# S7CAS-PLEIADES-CARTE-MERE_P07_DAC.net
KiCad netlist of a schematic drawn in Altium Designer
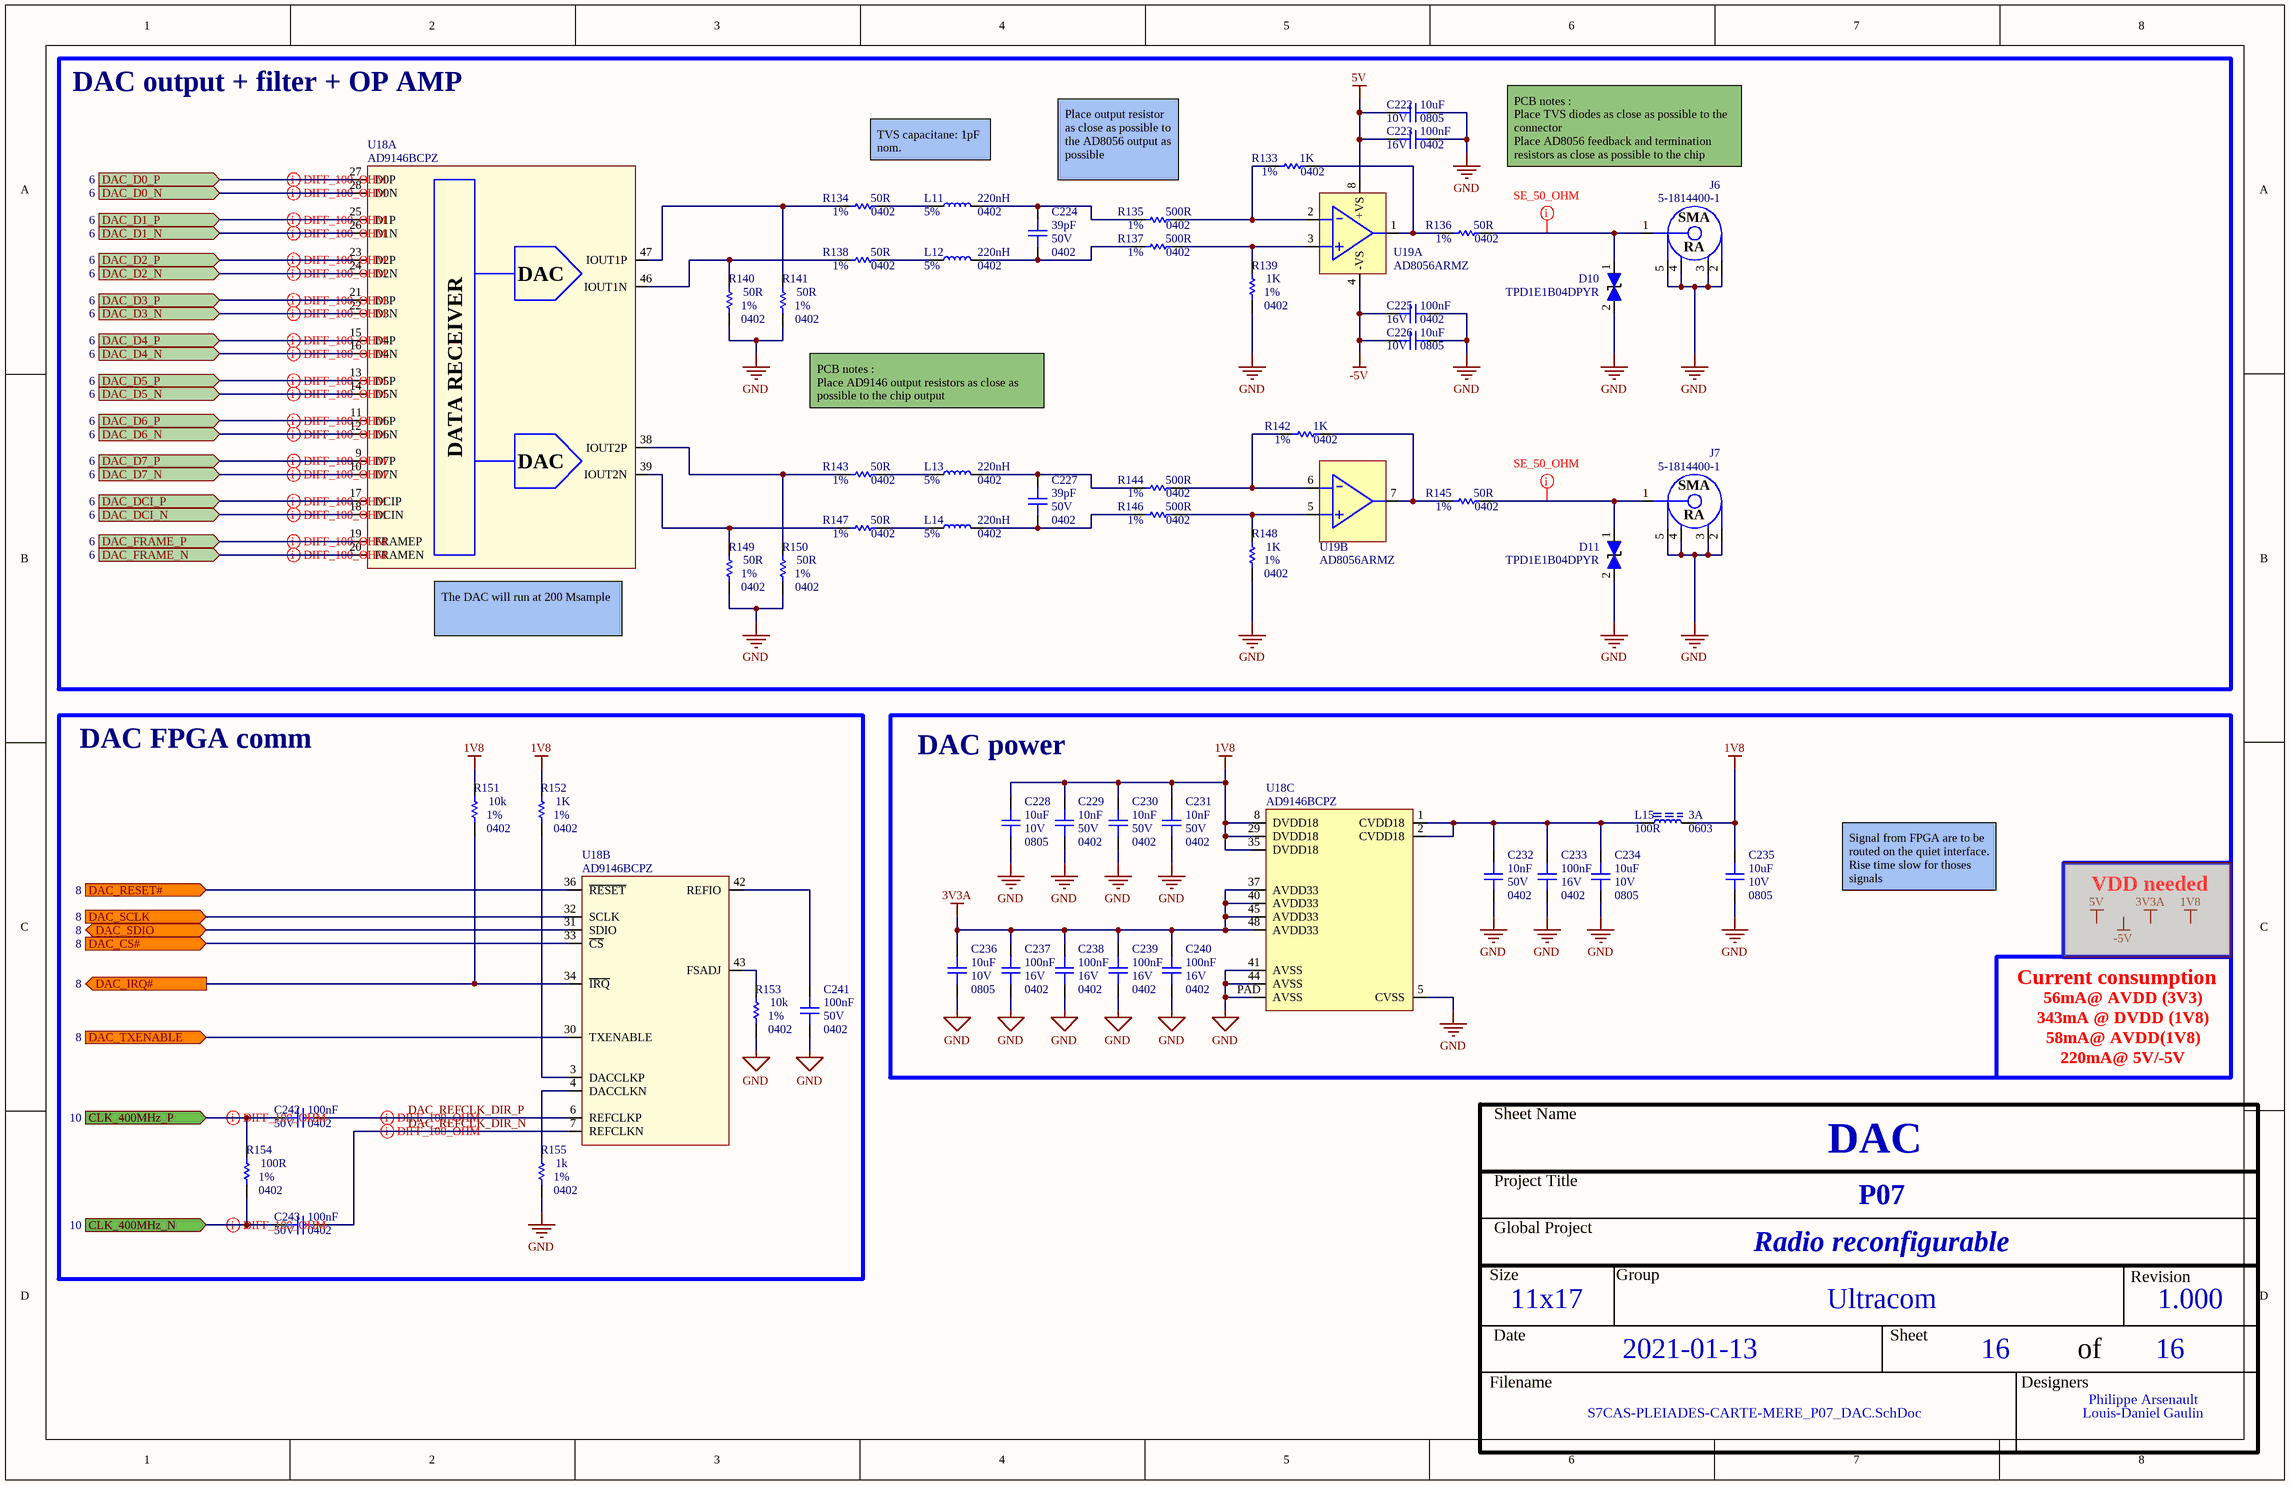
[diagram p0: S7CAS-PLEIADES-CARTE-MERE_P07_DAC.SchDoc]

(export (version "E")
  (design (tool "Eeschema 10.0.6"))
  (components
    (comp (ref "C222")
      (value "10uF")
      (footprint "CAP_0805")
      (description "CAP - 0805")
      (fields
        (field (name "MFG") "CL21B106KPQNNNE")
        (field (name "VOLTAGE") "10V")
        (field (name "PACKAGE") "0805")
        (field (name "CREATEDBY") "Jonathan Bouchard")
      )
      (libsource (lib "S7CAS_LIB2021") (part "CAP - 0805"))
    )
    (comp (ref "C223")
      (value "100nF")
      (footprint "CAP_0402")
      (description "CAP - 0402")
      (fields
        (field (name "MFG PART NUMBER") "CL05B104KO5NNNC")
        (field (name "VOLTAGE") "16V")
        (field (name "PACKAGE") "0402")
        (field (name "CREATEDBY") "Jonathan Bouchard")
      )
      (libsource (lib "S7CAS_LIB2021") (part "CAP - 0402"))
    )
    (comp (ref "C224")
      (value "39pF")
      (footprint "CAP_0402")
      (description "CAP - 0402")
      (fields
        (field (name "VOLTAGE") "50V")
        (field (name "PACKAGE") "0402")
        (field (name "CREATEDBY") "Jonathan Bouchard")
      )
      (libsource (lib "S7CAS_LIB2021") (part "CAP - 0402"))
    )
    (comp (ref "C225")
      (value "100nF")
      (footprint "CAP_0402")
      (description "CAP - 0402")
      (fields
        (field (name "MFG PART NUMBER") "CL05B104KO5NNNC")
        (field (name "VOLTAGE") "16V")
        (field (name "PACKAGE") "0402")
        (field (name "CREATEDBY") "Jonathan Bouchard")
      )
      (libsource (lib "S7CAS_LIB2021") (part "CAP - 0402"))
    )
    (comp (ref "C226")
      (value "10uF")
      (footprint "CAP_0805")
      (description "CAP - 0805")
      (fields
        (field (name "MFG") "CL21B106KPQNNNE")
        (field (name "VOLTAGE") "10V")
        (field (name "PACKAGE") "0805")
        (field (name "CREATEDBY") "Jonathan Bouchard")
      )
      (libsource (lib "S7CAS_LIB2021") (part "CAP - 0805"))
    )
    (comp (ref "C227")
      (value "39pF")
      (footprint "CAP_0402")
      (description "CAP - 0402")
      (fields
        (field (name "VOLTAGE") "50V")
        (field (name "PACKAGE") "0402")
        (field (name "CREATEDBY") "Jonathan Bouchard")
      )
      (libsource (lib "S7CAS_LIB2021") (part "CAP - 0402"))
    )
    (comp (ref "C228")
      (value "10uF")
      (footprint "CAP_0805")
      (description "CAP - 0805")
      (fields
        (field (name "MFG") "CL21B106KPQNNNE")
        (field (name "VOLTAGE") "10V")
        (field (name "PACKAGE") "0805")
        (field (name "CREATEDBY") "Jonathan Bouchard")
      )
      (libsource (lib "S7CAS_LIB2021") (part "CAP - 0805"))
    )
    (comp (ref "C229")
      (value "10nF")
      (footprint "CAP_0402")
      (description "CAP - 0402")
      (fields
        (field (name "MFG PART NUMBER") "CL05B103KB5NNNC")
        (field (name "VOLTAGE") "50V")
        (field (name "PACKAGE") "0402")
        (field (name "CREATEDBY") "Jonathan Bouchard")
      )
      (libsource (lib "S7CAS_LIB2021") (part "CAP - 0402"))
    )
    (comp (ref "C230")
      (value "10nF")
      (footprint "CAP_0402")
      (description "CAP - 0402")
      (fields
        (field (name "MFG PART NUMBER") "CL05B103KB5NNNC")
        (field (name "VOLTAGE") "50V")
        (field (name "PACKAGE") "0402")
        (field (name "CREATEDBY") "Jonathan Bouchard")
      )
      (libsource (lib "S7CAS_LIB2021") (part "CAP - 0402"))
    )
    (comp (ref "C231")
      (value "10nF")
      (footprint "CAP_0402")
      (description "CAP - 0402")
      (fields
        (field (name "MFG PART NUMBER") "CL05B103KB5NNNC")
        (field (name "VOLTAGE") "50V")
        (field (name "PACKAGE") "0402")
        (field (name "CREATEDBY") "Jonathan Bouchard")
      )
      (libsource (lib "S7CAS_LIB2021") (part "CAP - 0402"))
    )
    (comp (ref "C232")
      (value "10nF")
      (footprint "CAP_0402")
      (description "CAP - 0402")
      (fields
        (field (name "MFG PART NUMBER") "CL05B103KB5NNNC")
        (field (name "VOLTAGE") "50V")
        (field (name "PACKAGE") "0402")
        (field (name "CREATEDBY") "Jonathan Bouchard")
      )
      (libsource (lib "S7CAS_LIB2021") (part "CAP - 0402"))
    )
    (comp (ref "C233")
      (value "100nF")
      (footprint "CAP_0402")
      (description "CAP - 0402")
      (fields
        (field (name "MFG PART NUMBER") "CL05B104KO5NNNC")
        (field (name "VOLTAGE") "16V")
        (field (name "PACKAGE") "0402")
        (field (name "CREATEDBY") "Jonathan Bouchard")
      )
      (libsource (lib "S7CAS_LIB2021") (part "CAP - 0402"))
    )
    (comp (ref "C234")
      (value "10uF")
      (footprint "CAP_0805")
      (description "CAP - 0805")
      (fields
        (field (name "MFG") "CL21B106KPQNNNE")
        (field (name "VOLTAGE") "10V")
        (field (name "PACKAGE") "0805")
        (field (name "CREATEDBY") "Jonathan Bouchard")
      )
      (libsource (lib "S7CAS_LIB2021") (part "CAP - 0805"))
    )
    (comp (ref "C235")
      (value "10uF")
      (footprint "CAP_0805")
      (description "CAP - 0805")
      (fields
        (field (name "MFG") "CL21B106KPQNNNE")
        (field (name "VOLTAGE") "10V")
        (field (name "PACKAGE") "0805")
        (field (name "CREATEDBY") "Jonathan Bouchard")
      )
      (libsource (lib "S7CAS_LIB2021") (part "CAP - 0805"))
    )
    (comp (ref "C236")
      (value "10uF")
      (footprint "CAP_0805")
      (description "CAP - 0805")
      (fields
        (field (name "MFG") "CL21B106KPQNNNE")
        (field (name "VOLTAGE") "10V")
        (field (name "PACKAGE") "0805")
        (field (name "CREATEDBY") "Jonathan Bouchard")
      )
      (libsource (lib "S7CAS_LIB2021") (part "CAP - 0805"))
    )
    (comp (ref "C237")
      (value "100nF")
      (footprint "CAP_0402")
      (description "CAP - 0402")
      (fields
        (field (name "MFG PART NUMBER") "CL05B104KO5NNNC")
        (field (name "VOLTAGE") "16V")
        (field (name "PACKAGE") "0402")
        (field (name "CREATEDBY") "Jonathan Bouchard")
      )
      (libsource (lib "S7CAS_LIB2021") (part "CAP - 0402"))
    )
    (comp (ref "C238")
      (value "100nF")
      (footprint "CAP_0402")
      (description "CAP - 0402")
      (fields
        (field (name "MFG PART NUMBER") "CL05B104KO5NNNC")
        (field (name "VOLTAGE") "16V")
        (field (name "PACKAGE") "0402")
        (field (name "CREATEDBY") "Jonathan Bouchard")
      )
      (libsource (lib "S7CAS_LIB2021") (part "CAP - 0402"))
    )
    (comp (ref "C239")
      (value "100nF")
      (footprint "CAP_0402")
      (description "CAP - 0402")
      (fields
        (field (name "MFG PART NUMBER") "CL05B104KO5NNNC")
        (field (name "VOLTAGE") "16V")
        (field (name "PACKAGE") "0402")
        (field (name "CREATEDBY") "Jonathan Bouchard")
      )
      (libsource (lib "S7CAS_LIB2021") (part "CAP - 0402"))
    )
    (comp (ref "C240")
      (value "100nF")
      (footprint "CAP_0402")
      (description "CAP - 0402")
      (fields
        (field (name "MFG PART NUMBER") "CL05B104KO5NNNC")
        (field (name "VOLTAGE") "16V")
        (field (name "PACKAGE") "0402")
        (field (name "CREATEDBY") "Jonathan Bouchard")
      )
      (libsource (lib "S7CAS_LIB2021") (part "CAP - 0402"))
    )
    (comp (ref "C241")
      (value "100nF")
      (footprint "CAP_0402")
      (description "CAP - 0402")
      (fields
        (field (name "VOLTAGE") "50V")
        (field (name "PACKAGE") "0402")
        (field (name "CREATEDBY") "Jonathan Bouchard")
      )
      (libsource (lib "S7CAS_LIB2021") (part "CAP - 0402"))
    )
    (comp (ref "C242")
      (value "100nF")
      (footprint "CAP_0402")
      (description "CAP - 0402")
      (fields
        (field (name "VOLTAGE") "50V")
        (field (name "PACKAGE") "0402")
        (field (name "CREATEDBY") "Jonathan Bouchard")
      )
      (libsource (lib "S7CAS_LIB2021") (part "CAP - 0402"))
    )
    (comp (ref "C243")
      (value "100nF")
      (footprint "CAP_0402")
      (description "CAP - 0402")
      (fields
        (field (name "VOLTAGE") "50V")
        (field (name "PACKAGE") "0402")
        (field (name "CREATEDBY") "Jonathan Bouchard")
      )
      (libsource (lib "S7CAS_LIB2021") (part "CAP - 0402"))
    )
    (comp (ref "D10")
      (value "TPD1E1B04DPYR")
      (footprint "TVS_DATA_TPD1E1B04DPYR")
      (description "TVS - TVS DIODE 3.6V 8.5V - 0402")
      (fields
        (field (name "CREATEDBY/DATE") "Keven Deslandes - 2018/10/19")
        (field (name "VERIFIEDBY") "Caroline Paulin - 28 janv 2019")
      )
      (libsource (lib "S7CAS_LIB2021") (part "TVS_DATA_TPD1E1B04DPYR"))
    )
    (comp (ref "D11")
      (value "TPD1E1B04DPYR")
      (footprint "TVS_DATA_TPD1E1B04DPYR")
      (description "TVS - TVS DIODE 3.6V 8.5V - 0402")
      (fields
        (field (name "CREATEDBY/DATE") "Keven Deslandes - 2018/10/19")
        (field (name "VERIFIEDBY") "Caroline Paulin - 28 janv 2019")
      )
      (libsource (lib "S7CAS_LIB2021") (part "TVS_DATA_TPD1E1B04DPYR"))
    )
    (comp (ref "J6")
      (value "5-1814400-1")
      (footprint "CONN_SMA_5-1814400-1")
      (description "CONN -  SMA JACK R/A 50 OHM - TH")
      (fields
        (field (name "MFG") "TE Connectivity AMP Connectors")
        (field (name "CREATEDBY") "Jonathan Bouchard")
      )
      (libsource (lib "S7CAS_LIB2021") (part "CONN_SMA_5-1814400-1"))
    )
    (comp (ref "J7")
      (value "5-1814400-1")
      (footprint "CONN_SMA_5-1814400-1")
      (description "CONN -  SMA JACK R/A 50 OHM - TH")
      (fields
        (field (name "MFG") "TE Connectivity AMP Connectors")
        (field (name "CREATEDBY") "Jonathan Bouchard")
      )
      (libsource (lib "S7CAS_LIB2021") (part "CONN_SMA_5-1814400-1"))
    )
    (comp (ref "L11")
      (value "220nH")
      (footprint "IND_0402")
      (description "IND_0402")
      (fields
        (field (name "PRECISION") "5%")
        (field (name "PACKAGE") "0402")
        (field (name "CREATEDBY") "Jonathan Bouchard")
      )
      (libsource (lib "S7CAS_P07") (part "IND_0402"))
    )
    (comp (ref "L12")
      (value "220nH")
      (footprint "IND_0402")
      (description "IND_0402")
      (fields
        (field (name "PRECISION") "5%")
        (field (name "PACKAGE") "0402")
        (field (name "CREATEDBY") "Jonathan Bouchard")
      )
      (libsource (lib "S7CAS_P07") (part "IND_0402"))
    )
    (comp (ref "L13")
      (value "220nH")
      (footprint "IND_0402")
      (description "IND_0402")
      (fields
        (field (name "PRECISION") "5%")
        (field (name "PACKAGE") "0402")
        (field (name "CREATEDBY") "Jonathan Bouchard")
      )
      (libsource (lib "S7CAS_P07") (part "IND_0402"))
    )
    (comp (ref "L14")
      (value "220nH")
      (footprint "IND_0402")
      (description "IND_0402")
      (fields
        (field (name "PRECISION") "5%")
        (field (name "PACKAGE") "0402")
        (field (name "CREATEDBY") "Jonathan Bouchard")
      )
      (libsource (lib "S7CAS_P07") (part "IND_0402"))
    )
    (comp (ref "L15")
      (value "100R")
      (footprint "FER_0603")
      (description "FER - 0603")
      (fields
        (field (name "CURRENT") "3A")
        (field (name "PACKAGE") "0603")
        (field (name "CREATEDBY") "Jonathan Bouchard")
      )
      (libsource (lib "S7CAS_LIB2021") (part "FER - 0603"))
    )
    (comp (ref "R133")
      (value "1K")
      (footprint "RES_0402")
      (description "RES - 0402")
      (fields
        (field (name "VOLTAGE") "50V")
        (field (name "POWER") "1/16W")
        (field (name "PACKAGE") "0402")
        (field (name "PRECISION") "1%")
        (field (name "CREATEDBY") "Jonathan Bouchard")
      )
      (libsource (lib "S7CAS_LIB2021") (part "RES - 0402"))
    )
    (comp (ref "R134")
      (value "50R")
      (footprint "RES_0402")
      (description "RES - 0402")
      (fields
        (field (name "VOLTAGE") "50V")
        (field (name "POWER") "1/16W")
        (field (name "PACKAGE") "0402")
        (field (name "PRECISION") "1%")
        (field (name "CREATEDBY") "Jonathan Bouchard")
      )
      (libsource (lib "S7CAS_LIB2021") (part "RES - 0402"))
    )
    (comp (ref "R135")
      (value "500R")
      (footprint "RES_0402")
      (description "RES - 0402")
      (fields
        (field (name "VOLTAGE") "50V")
        (field (name "POWER") "1/16W")
        (field (name "PACKAGE") "0402")
        (field (name "PRECISION") "1%")
        (field (name "CREATEDBY") "Jonathan Bouchard")
      )
      (libsource (lib "S7CAS_LIB2021") (part "RES - 0402"))
    )
    (comp (ref "R136")
      (value "50R")
      (footprint "RES_0402")
      (description "RES - 0402")
      (fields
        (field (name "VOLTAGE") "50V")
        (field (name "POWER") "1/16W")
        (field (name "PACKAGE") "0402")
        (field (name "PRECISION") "1%")
        (field (name "CREATEDBY") "Jonathan Bouchard")
      )
      (libsource (lib "S7CAS_LIB2021") (part "RES - 0402"))
    )
    (comp (ref "R137")
      (value "500R")
      (footprint "RES_0402")
      (description "RES - 0402")
      (fields
        (field (name "VOLTAGE") "50V")
        (field (name "POWER") "1/16W")
        (field (name "PACKAGE") "0402")
        (field (name "PRECISION") "1%")
        (field (name "CREATEDBY") "Jonathan Bouchard")
      )
      (libsource (lib "S7CAS_LIB2021") (part "RES - 0402"))
    )
    (comp (ref "R138")
      (value "50R")
      (footprint "RES_0402")
      (description "RES - 0402")
      (fields
        (field (name "VOLTAGE") "50V")
        (field (name "POWER") "1/16W")
        (field (name "PACKAGE") "0402")
        (field (name "PRECISION") "1%")
        (field (name "CREATEDBY") "Jonathan Bouchard")
      )
      (libsource (lib "S7CAS_LIB2021") (part "RES - 0402"))
    )
    (comp (ref "R139")
      (value "1K")
      (footprint "RES_0402")
      (description "RES - 0402")
      (fields
        (field (name "VOLTAGE") "50V")
        (field (name "POWER") "1/16W")
        (field (name "PACKAGE") "0402")
        (field (name "PRECISION") "1%")
        (field (name "CREATEDBY") "Jonathan Bouchard")
      )
      (libsource (lib "S7CAS_LIB2021") (part "RES - 0402"))
    )
    (comp (ref "R140")
      (value "50R")
      (footprint "RES_0402")
      (description "RES - 0402")
      (fields
        (field (name "VOLTAGE") "50V")
        (field (name "POWER") "1/16W")
        (field (name "PACKAGE") "0402")
        (field (name "PRECISION") "1%")
        (field (name "CREATEDBY") "Jonathan Bouchard")
      )
      (libsource (lib "S7CAS_LIB2021") (part "RES - 0402"))
    )
    (comp (ref "R141")
      (value "50R")
      (footprint "RES_0402")
      (description "RES - 0402")
      (fields
        (field (name "VOLTAGE") "50V")
        (field (name "POWER") "1/16W")
        (field (name "PACKAGE") "0402")
        (field (name "PRECISION") "1%")
        (field (name "CREATEDBY") "Jonathan Bouchard")
      )
      (libsource (lib "S7CAS_LIB2021") (part "RES - 0402"))
    )
    (comp (ref "R142")
      (value "1K")
      (footprint "RES_0402")
      (description "RES - 0402")
      (fields
        (field (name "VOLTAGE") "50V")
        (field (name "POWER") "1/16W")
        (field (name "PACKAGE") "0402")
        (field (name "PRECISION") "1%")
        (field (name "CREATEDBY") "Jonathan Bouchard")
      )
      (libsource (lib "S7CAS_LIB2021") (part "RES - 0402"))
    )
    (comp (ref "R143")
      (value "50R")
      (footprint "RES_0402")
      (description "RES - 0402")
      (fields
        (field (name "VOLTAGE") "50V")
        (field (name "POWER") "1/16W")
        (field (name "PACKAGE") "0402")
        (field (name "PRECISION") "1%")
        (field (name "CREATEDBY") "Jonathan Bouchard")
      )
      (libsource (lib "S7CAS_LIB2021") (part "RES - 0402"))
    )
    (comp (ref "R144")
      (value "500R")
      (footprint "RES_0402")
      (description "RES - 0402")
      (fields
        (field (name "VOLTAGE") "50V")
        (field (name "POWER") "1/16W")
        (field (name "PACKAGE") "0402")
        (field (name "PRECISION") "1%")
        (field (name "CREATEDBY") "Jonathan Bouchard")
      )
      (libsource (lib "S7CAS_LIB2021") (part "RES - 0402"))
    )
    (comp (ref "R145")
      (value "50R")
      (footprint "RES_0402")
      (description "RES - 0402")
      (fields
        (field (name "VOLTAGE") "50V")
        (field (name "POWER") "1/16W")
        (field (name "PACKAGE") "0402")
        (field (name "PRECISION") "1%")
        (field (name "CREATEDBY") "Jonathan Bouchard")
      )
      (libsource (lib "S7CAS_LIB2021") (part "RES - 0402"))
    )
    (comp (ref "R146")
      (value "500R")
      (footprint "RES_0402")
      (description "RES - 0402")
      (fields
        (field (name "VOLTAGE") "50V")
        (field (name "POWER") "1/16W")
        (field (name "PACKAGE") "0402")
        (field (name "PRECISION") "1%")
        (field (name "CREATEDBY") "Jonathan Bouchard")
      )
      (libsource (lib "S7CAS_LIB2021") (part "RES - 0402"))
    )
    (comp (ref "R147")
      (value "50R")
      (footprint "RES_0402")
      (description "RES - 0402")
      (fields
        (field (name "VOLTAGE") "50V")
        (field (name "POWER") "1/16W")
        (field (name "PACKAGE") "0402")
        (field (name "PRECISION") "1%")
        (field (name "CREATEDBY") "Jonathan Bouchard")
      )
      (libsource (lib "S7CAS_LIB2021") (part "RES - 0402"))
    )
    (comp (ref "R148")
      (value "1K")
      (footprint "RES_0402")
      (description "RES - 0402")
      (fields
        (field (name "VOLTAGE") "50V")
        (field (name "POWER") "1/16W")
        (field (name "PACKAGE") "0402")
        (field (name "PRECISION") "1%")
        (field (name "CREATEDBY") "Jonathan Bouchard")
      )
      (libsource (lib "S7CAS_LIB2021") (part "RES - 0402"))
    )
    (comp (ref "R149")
      (value "50R")
      (footprint "RES_0402")
      (description "RES - 0402")
      (fields
        (field (name "VOLTAGE") "50V")
        (field (name "POWER") "1/16W")
        (field (name "PACKAGE") "0402")
        (field (name "PRECISION") "1%")
        (field (name "CREATEDBY") "Jonathan Bouchard")
      )
      (libsource (lib "S7CAS_LIB2021") (part "RES - 0402"))
    )
    (comp (ref "R150")
      (value "50R")
      (footprint "RES_0402")
      (description "RES - 0402")
      (fields
        (field (name "VOLTAGE") "50V")
        (field (name "POWER") "1/16W")
        (field (name "PACKAGE") "0402")
        (field (name "PRECISION") "1%")
        (field (name "CREATEDBY") "Jonathan Bouchard")
      )
      (libsource (lib "S7CAS_LIB2021") (part "RES - 0402"))
    )
    (comp (ref "R151")
      (value "10k")
      (footprint "RES_0402")
      (description "RES - 0402")
      (fields
        (field (name "VOLTAGE") "50V")
        (field (name "POWER") "1/16W")
        (field (name "PACKAGE") "0402")
        (field (name "PRECISION") "1%")
        (field (name "CREATEDBY") "Jonathan Bouchard")
      )
      (libsource (lib "S7CAS_LIB2021") (part "RES - 0402"))
    )
    (comp (ref "R152")
      (value "1K")
      (footprint "RES_0402")
      (description "RES - 0402")
      (fields
        (field (name "VOLTAGE") "50V")
        (field (name "POWER") "1/16W")
        (field (name "PACKAGE") "0402")
        (field (name "PRECISION") "1%")
        (field (name "CREATEDBY") "Jonathan Bouchard")
      )
      (libsource (lib "S7CAS_LIB2021") (part "RES - 0402"))
    )
    (comp (ref "R153")
      (value "10k")
      (footprint "RES_0402")
      (description "RES - 0402")
      (fields
        (field (name "VOLTAGE") "50V")
        (field (name "POWER") "1/16W")
        (field (name "PACKAGE") "0402")
        (field (name "PRECISION") "1%")
        (field (name "CREATEDBY") "Jonathan Bouchard")
      )
      (libsource (lib "S7CAS_LIB2021") (part "RES - 0402"))
    )
    (comp (ref "R154")
      (value "100R")
      (footprint "RES_0402")
      (description "RES - 0402")
      (fields
        (field (name "VOLTAGE") "50V")
        (field (name "POWER") "1/16W")
        (field (name "PACKAGE") "0402")
        (field (name "PRECISION") "1%")
        (field (name "CREATEDBY") "Jonathan Bouchard")
      )
      (libsource (lib "S7CAS_LIB2021") (part "RES - 0402"))
    )
    (comp (ref "R155")
      (value "1k")
      (footprint "RES_0402")
      (description "RES - 0402")
      (fields
        (field (name "VOLTAGE") "50V")
        (field (name "POWER") "1/16W")
        (field (name "PACKAGE") "0402")
        (field (name "PRECISION") "1%")
        (field (name "CREATEDBY") "Jonathan Bouchard")
      )
      (libsource (lib "S7CAS_LIB2021") (part "RES - 0402"))
    )
    (comp (ref "U18")
      (value "AD9146BCPZ")
      (footprint "DAC_AD9146BCPZ")
      (description "DAC - 16BIT SRL HIGH SPEED - QFN-48")
      (fields
        (field (name "VOLTAGE") "3.13 V ~ 3.47 V / 1.71 V ~ 1.89 V")
        (field (name "MFG") "Analog Devices Inc.")
        (field (name "CREATEDBY") "Jonathan Bouchard")
      )
      (libsource (lib "S7CAS_LIB2021") (part "DAC_AD9146BCPZ"))
    )
    (comp (ref "U19")
      (value "AD8056ARMZ")
      (footprint "OPAMP_AD8056ARMZ")
      (description "OPAMP - VFB 300MHZ - 8MSOP")
      (fields
        (field (name "VOLTAGE") "8 V ~ 12 V, ±4 V ~ 6 V")
        (field (name "MFG") "Analog Devices")
        (field (name "CREATEDBY") "Jonathan Bouchard")
      )
      (libsource (lib "S7CAS_LIB2021") (part "OPAMP_AD8056ARMZ"))
    )
  )
  (nets
    (net (code "1") (name "-5V") (class "Default")
      (node (ref "C225") (pin "2") (pinfunction "2_2") (pintype "passive"))
      (node (ref "C226") (pin "2") (pinfunction "2_2") (pintype "passive"))
      (node (ref "U19") (pin "4") (pinfunction "-VS_4") (pintype "passive"))
    )
    (net (code "2") (name "/CLK_400MHz_N") (class "Default")
      (node (ref "C243") (pin "2") (pinfunction "2_2") (pintype "passive"))
      (node (ref "R154") (pin "1") (pinfunction "1_1") (pintype "passive"))
    )
    (net (code "3") (name "/CLK_400MHz_P") (class "Default")
      (node (ref "C242") (pin "2") (pinfunction "2_2") (pintype "passive"))
      (node (ref "R154") (pin "2") (pinfunction "2_2") (pintype "passive"))
    )
    (net (code "4") (name "/DAC_CS#") (class "Default")
      (node (ref "U18") (pin "33") (pinfunction "~{CS}_33") (pintype "passive"))
    )
    (net (code "5") (name "/DAC_D0_N") (class "Default")
      (node (ref "U18") (pin "28") (pinfunction "D0N_28") (pintype "passive"))
    )
    (net (code "6") (name "/DAC_D0_P") (class "Default")
      (node (ref "U18") (pin "27") (pinfunction "D0P_27") (pintype "passive"))
    )
    (net (code "7") (name "/DAC_D1_N") (class "Default")
      (node (ref "U18") (pin "26") (pinfunction "D1N_26") (pintype "passive"))
    )
    (net (code "8") (name "/DAC_D1_P") (class "Default")
      (node (ref "U18") (pin "25") (pinfunction "D1P_25") (pintype "passive"))
    )
    (net (code "9") (name "/DAC_D2_N") (class "Default")
      (node (ref "U18") (pin "24") (pinfunction "D2N_24") (pintype "passive"))
    )
    (net (code "10") (name "/DAC_D2_P") (class "Default")
      (node (ref "U18") (pin "23") (pinfunction "D2P_23") (pintype "passive"))
    )
    (net (code "11") (name "/DAC_D3_N") (class "Default")
      (node (ref "U18") (pin "22") (pinfunction "D3N_22") (pintype "passive"))
    )
    (net (code "12") (name "/DAC_D3_P") (class "Default")
      (node (ref "U18") (pin "21") (pinfunction "D3P_21") (pintype "passive"))
    )
    (net (code "13") (name "/DAC_D4_N") (class "Default")
      (node (ref "U18") (pin "16") (pinfunction "D4N_16") (pintype "passive"))
    )
    (net (code "14") (name "/DAC_D4_P") (class "Default")
      (node (ref "U18") (pin "15") (pinfunction "D4P_15") (pintype "passive"))
    )
    (net (code "15") (name "/DAC_D5_N") (class "Default")
      (node (ref "U18") (pin "14") (pinfunction "D5N_14") (pintype "passive"))
    )
    (net (code "16") (name "/DAC_D5_P") (class "Default")
      (node (ref "U18") (pin "13") (pinfunction "D5P_13") (pintype "passive"))
    )
    (net (code "17") (name "/DAC_D6_N") (class "Default")
      (node (ref "U18") (pin "12") (pinfunction "D6N_12") (pintype "passive"))
    )
    (net (code "18") (name "/DAC_D6_P") (class "Default")
      (node (ref "U18") (pin "11") (pinfunction "D6P_11") (pintype "passive"))
    )
    (net (code "19") (name "/DAC_D7_N") (class "Default")
      (node (ref "U18") (pin "10") (pinfunction "D7N_10") (pintype "passive"))
    )
    (net (code "20") (name "/DAC_D7_P") (class "Default")
      (node (ref "U18") (pin "9") (pinfunction "D7P_9") (pintype "passive"))
    )
    (net (code "21") (name "/DAC_DCI_N") (class "Default")
      (node (ref "U18") (pin "18") (pinfunction "DCIN_18") (pintype "passive"))
    )
    (net (code "22") (name "/DAC_DCI_P") (class "Default")
      (node (ref "U18") (pin "17") (pinfunction "DCIP_17") (pintype "passive"))
    )
    (net (code "23") (name "/DAC_FRAME_N") (class "Default")
      (node (ref "U18") (pin "20") (pinfunction "FRAMEN_20") (pintype "passive"))
    )
    (net (code "24") (name "/DAC_FRAME_P") (class "Default")
      (node (ref "U18") (pin "19") (pinfunction "FRAMEP_19") (pintype "passive"))
    )
    (net (code "25") (name "/DAC_IRQ#") (class "Default")
      (node (ref "R151") (pin "1") (pinfunction "1_1") (pintype "passive"))
      (node (ref "U18") (pin "34") (pinfunction "~{IRQ}_34") (pintype "passive"))
    )
    (net (code "26") (name "/DAC_REFCLK_DIR_N") (class "Default")
      (node (ref "C243") (pin "1") (pinfunction "1_1") (pintype "passive"))
      (node (ref "U18") (pin "7") (pinfunction "REFCLKN_7") (pintype "passive"))
    )
    (net (code "27") (name "/DAC_REFCLK_DIR_P") (class "Default")
      (node (ref "C242") (pin "1") (pinfunction "1_1") (pintype "passive"))
      (node (ref "U18") (pin "6") (pinfunction "REFCLKP_6") (pintype "passive"))
    )
    (net (code "28") (name "/DAC_RESET#") (class "Default")
      (node (ref "U18") (pin "36") (pinfunction "~{RESET}_36") (pintype "passive"))
    )
    (net (code "29") (name "/DAC_SCLK") (class "Default")
      (node (ref "U18") (pin "32") (pinfunction "SCLK_32") (pintype "passive"))
    )
    (net (code "30") (name "/DAC_SDIO") (class "Default")
      (node (ref "U18") (pin "31") (pinfunction "SDIO_31") (pintype "passive"))
    )
    (net (code "31") (name "/DAC_TXENABLE") (class "Default")
      (node (ref "U18") (pin "30") (pinfunction "TXENABLE_30") (pintype "passive"))
    )
    (net (code "32") (name "1V8") (class "Default")
      (node (ref "C228") (pin "2") (pinfunction "2_2") (pintype "passive"))
      (node (ref "C229") (pin "2") (pinfunction "2_2") (pintype "passive"))
      (node (ref "C230") (pin "2") (pinfunction "2_2") (pintype "passive"))
      (node (ref "C231") (pin "2") (pinfunction "2_2") (pintype "passive"))
      (node (ref "C235") (pin "2") (pinfunction "2_2") (pintype "passive"))
      (node (ref "L15") (pin "1") (pinfunction "1_1") (pintype "passive"))
      (node (ref "R151") (pin "2") (pinfunction "2_2") (pintype "passive"))
      (node (ref "R152") (pin "2") (pinfunction "2_2") (pintype "passive"))
      (node (ref "U18") (pin "29") (pinfunction "DVDD18_29") (pintype "passive"))
      (node (ref "U18") (pin "35") (pinfunction "DVDD18_35") (pintype "passive"))
      (node (ref "U18") (pin "8") (pinfunction "DVDD18_8") (pintype "passive"))
    )
    (net (code "33") (name "3V3A") (class "Default")
      (node (ref "C236") (pin "2") (pinfunction "2_2") (pintype "passive"))
      (node (ref "C237") (pin "2") (pinfunction "2_2") (pintype "passive"))
      (node (ref "C238") (pin "2") (pinfunction "2_2") (pintype "passive"))
      (node (ref "C239") (pin "2") (pinfunction "2_2") (pintype "passive"))
      (node (ref "C240") (pin "2") (pinfunction "2_2") (pintype "passive"))
      (node (ref "U18") (pin "37") (pinfunction "AVDD33_37") (pintype "passive"))
      (node (ref "U18") (pin "40") (pinfunction "AVDD33_40") (pintype "passive"))
      (node (ref "U18") (pin "45") (pinfunction "AVDD33_45") (pintype "passive"))
      (node (ref "U18") (pin "48") (pinfunction "AVDD33_48") (pintype "passive"))
    )
    (net (code "34") (name "5V") (class "Default")
      (node (ref "C222") (pin "2") (pinfunction "2_2") (pintype "passive"))
      (node (ref "C223") (pin "2") (pinfunction "2_2") (pintype "passive"))
      (node (ref "U19") (pin "8") (pinfunction "+VS_8") (pintype "passive"))
    )
    (net (code "35") (name "GND") (class "Default")
      (node (ref "C222") (pin "1") (pinfunction "1_1") (pintype "passive"))
      (node (ref "C223") (pin "1") (pinfunction "1_1") (pintype "passive"))
      (node (ref "C225") (pin "1") (pinfunction "1_1") (pintype "passive"))
      (node (ref "C226") (pin "1") (pinfunction "1_1") (pintype "passive"))
      (node (ref "C228") (pin "1") (pinfunction "1_1") (pintype "passive"))
      (node (ref "C229") (pin "1") (pinfunction "1_1") (pintype "passive"))
      (node (ref "C230") (pin "1") (pinfunction "1_1") (pintype "passive"))
      (node (ref "C231") (pin "1") (pinfunction "1_1") (pintype "passive"))
      (node (ref "C232") (pin "1") (pinfunction "1_1") (pintype "passive"))
      (node (ref "C233") (pin "1") (pinfunction "1_1") (pintype "passive"))
      (node (ref "C234") (pin "1") (pinfunction "1_1") (pintype "passive"))
      (node (ref "C235") (pin "1") (pinfunction "1_1") (pintype "passive"))
      (node (ref "C236") (pin "1") (pinfunction "1_1") (pintype "passive"))
      (node (ref "C237") (pin "1") (pinfunction "1_1") (pintype "passive"))
      (node (ref "C238") (pin "1") (pinfunction "1_1") (pintype "passive"))
      (node (ref "C239") (pin "1") (pinfunction "1_1") (pintype "passive"))
      (node (ref "C240") (pin "1") (pinfunction "1_1") (pintype "passive"))
      (node (ref "C241") (pin "1") (pinfunction "1_1") (pintype "passive"))
      (node (ref "D10") (pin "2") (pinfunction "i/o_2") (pintype "passive"))
      (node (ref "D11") (pin "2") (pinfunction "i/o_2") (pintype "passive"))
      (node (ref "J6") (pin "2") (pinfunction "2_2") (pintype "passive"))
      (node (ref "J6") (pin "3") (pinfunction "3_3") (pintype "passive"))
      (node (ref "J6") (pin "4") (pinfunction "4_4") (pintype "passive"))
      (node (ref "J6") (pin "5") (pinfunction "5_5") (pintype "passive"))
      (node (ref "J7") (pin "2") (pinfunction "2_2") (pintype "passive"))
      (node (ref "J7") (pin "3") (pinfunction "3_3") (pintype "passive"))
      (node (ref "J7") (pin "4") (pinfunction "4_4") (pintype "passive"))
      (node (ref "J7") (pin "5") (pinfunction "5_5") (pintype "passive"))
      (node (ref "R139") (pin "1") (pinfunction "1_1") (pintype "passive"))
      (node (ref "R140") (pin "1") (pinfunction "1_1") (pintype "passive"))
      (node (ref "R141") (pin "1") (pinfunction "1_1") (pintype "passive"))
      (node (ref "R148") (pin "1") (pinfunction "1_1") (pintype "passive"))
      (node (ref "R149") (pin "1") (pinfunction "1_1") (pintype "passive"))
      (node (ref "R150") (pin "1") (pinfunction "1_1") (pintype "passive"))
      (node (ref "R153") (pin "1") (pinfunction "1_1") (pintype "passive"))
      (node (ref "R155") (pin "1") (pinfunction "1_1") (pintype "passive"))
      (node (ref "U18") (pin "41") (pinfunction "AVSS_41") (pintype "passive"))
      (node (ref "U18") (pin "44") (pinfunction "AVSS_44") (pintype "passive"))
      (node (ref "U18") (pin "5") (pinfunction "CVSS_5") (pintype "passive"))
      (node (ref "U18") (pin "PAD") (pinfunction "AVSS_PAD") (pintype "passive"))
    )
    (net (code "36") (name "Net-(C224-Pad1)") (class "Default")
      (node (ref "C224") (pin "1") (pinfunction "1_1") (pintype "passive"))
      (node (ref "L12") (pin "1") (pinfunction "1_1") (pintype "passive"))
      (node (ref "R137") (pin "2") (pinfunction "2_2") (pintype "passive"))
    )
    (net (code "37") (name "Net-(C224-Pad2)") (class "Default")
      (node (ref "C224") (pin "2") (pinfunction "2_2") (pintype "passive"))
      (node (ref "L11") (pin "1") (pinfunction "1_1") (pintype "passive"))
      (node (ref "R135") (pin "2") (pinfunction "2_2") (pintype "passive"))
    )
    (net (code "38") (name "Net-(C227-Pad1)") (class "Default")
      (node (ref "C227") (pin "1") (pinfunction "1_1") (pintype "passive"))
      (node (ref "L14") (pin "1") (pinfunction "1_1") (pintype "passive"))
      (node (ref "R146") (pin "2") (pinfunction "2_2") (pintype "passive"))
    )
    (net (code "39") (name "Net-(C227-Pad2)") (class "Default")
      (node (ref "C227") (pin "2") (pinfunction "2_2") (pintype "passive"))
      (node (ref "L13") (pin "1") (pinfunction "1_1") (pintype "passive"))
      (node (ref "R144") (pin "2") (pinfunction "2_2") (pintype "passive"))
    )
    (net (code "40") (name "Net-(C232-Pad2)") (class "Default")
      (node (ref "C232") (pin "2") (pinfunction "2_2") (pintype "passive"))
      (node (ref "C233") (pin "2") (pinfunction "2_2") (pintype "passive"))
      (node (ref "C234") (pin "2") (pinfunction "2_2") (pintype "passive"))
      (node (ref "L15") (pin "2") (pinfunction "2_2") (pintype "passive"))
      (node (ref "U18") (pin "1") (pinfunction "CVDD18_1") (pintype "passive"))
      (node (ref "U18") (pin "2") (pinfunction "CVDD18_2") (pintype "passive"))
    )
    (net (code "41") (name "Net-(D10-i{slash}o-Pad1)") (class "Default")
      (node (ref "D10") (pin "1") (pinfunction "i/o_1") (pintype "passive"))
      (node (ref "J6") (pin "1") (pinfunction "1_1") (pintype "passive"))
      (node (ref "R136") (pin "1") (pinfunction "1_1") (pintype "passive"))
    )
    (net (code "42") (name "Net-(D11-i{slash}o-Pad1)") (class "Default")
      (node (ref "D11") (pin "1") (pinfunction "i/o_1") (pintype "passive"))
      (node (ref "J7") (pin "1") (pinfunction "1_1") (pintype "passive"))
      (node (ref "R145") (pin "1") (pinfunction "1_1") (pintype "passive"))
    )
    (net (code "43") (name "Net-(L11-Pad2)") (class "Default")
      (node (ref "L11") (pin "2") (pinfunction "2_2") (pintype "passive"))
      (node (ref "R134") (pin "1") (pinfunction "1_1") (pintype "passive"))
    )
    (net (code "44") (name "Net-(L12-Pad2)") (class "Default")
      (node (ref "L12") (pin "2") (pinfunction "2_2") (pintype "passive"))
      (node (ref "R138") (pin "1") (pinfunction "1_1") (pintype "passive"))
    )
    (net (code "45") (name "Net-(L13-Pad2)") (class "Default")
      (node (ref "L13") (pin "2") (pinfunction "2_2") (pintype "passive"))
      (node (ref "R143") (pin "1") (pinfunction "1_1") (pintype "passive"))
    )
    (net (code "46") (name "Net-(L14-Pad2)") (class "Default")
      (node (ref "L14") (pin "2") (pinfunction "2_2") (pintype "passive"))
      (node (ref "R147") (pin "1") (pinfunction "1_1") (pintype "passive"))
    )
    (net (code "47") (name "Net-(U18A-IOUT1N)") (class "Default")
      (node (ref "R138") (pin "2") (pinfunction "2_2") (pintype "passive"))
      (node (ref "R140") (pin "2") (pinfunction "2_2") (pintype "passive"))
      (node (ref "U18") (pin "46") (pinfunction "IOUT1N_46") (pintype "passive"))
    )
    (net (code "48") (name "Net-(U18A-IOUT1P)") (class "Default")
      (node (ref "R134") (pin "2") (pinfunction "2_2") (pintype "passive"))
      (node (ref "R141") (pin "2") (pinfunction "2_2") (pintype "passive"))
      (node (ref "U18") (pin "47") (pinfunction "IOUT1P_47") (pintype "passive"))
    )
    (net (code "49") (name "Net-(U18A-IOUT2N)") (class "Default")
      (node (ref "R147") (pin "2") (pinfunction "2_2") (pintype "passive"))
      (node (ref "R149") (pin "2") (pinfunction "2_2") (pintype "passive"))
      (node (ref "U18") (pin "39") (pinfunction "IOUT2N_39") (pintype "passive"))
    )
    (net (code "50") (name "Net-(U18A-IOUT2P)") (class "Default")
      (node (ref "R143") (pin "2") (pinfunction "2_2") (pintype "passive"))
      (node (ref "R150") (pin "2") (pinfunction "2_2") (pintype "passive"))
      (node (ref "U18") (pin "38") (pinfunction "IOUT2P_38") (pintype "passive"))
    )
    (net (code "51") (name "Net-(U18B-DACCLKN)") (class "Default")
      (node (ref "R155") (pin "2") (pinfunction "2_2") (pintype "passive"))
      (node (ref "U18") (pin "4") (pinfunction "DACCLKN_4") (pintype "passive"))
    )
    (net (code "52") (name "Net-(U18B-DACCLKP)") (class "Default")
      (node (ref "R152") (pin "1") (pinfunction "1_1") (pintype "passive"))
      (node (ref "U18") (pin "3") (pinfunction "DACCLKP_3") (pintype "passive"))
    )
    (net (code "53") (name "Net-(U18B-FSADJ)") (class "Default")
      (node (ref "R153") (pin "2") (pinfunction "2_2") (pintype "passive"))
      (node (ref "U18") (pin "43") (pinfunction "FSADJ_43") (pintype "passive"))
    )
    (net (code "54") (name "Net-(U18B-REFIO)") (class "Default")
      (node (ref "C241") (pin "2") (pinfunction "2_2") (pintype "passive"))
      (node (ref "U18") (pin "42") (pinfunction "REFIO_42") (pintype "passive"))
    )
    (net (code "55") (name "Net-(U19A-+IN1)") (class "Default")
      (node (ref "R137") (pin "1") (pinfunction "1_1") (pintype "passive"))
      (node (ref "R139") (pin "2") (pinfunction "2_2") (pintype "passive"))
      (node (ref "U19") (pin "3") (pinfunction "+IN1_3") (pintype "passive"))
    )
    (net (code "56") (name "Net-(U19A--IN1)") (class "Default")
      (node (ref "R133") (pin "2") (pinfunction "2_2") (pintype "passive"))
      (node (ref "R135") (pin "1") (pinfunction "1_1") (pintype "passive"))
      (node (ref "U19") (pin "2") (pinfunction "-IN1_2") (pintype "passive"))
    )
    (net (code "57") (name "Net-(U19A-OUT1)") (class "Default")
      (node (ref "R133") (pin "1") (pinfunction "1_1") (pintype "passive"))
      (node (ref "R136") (pin "2") (pinfunction "2_2") (pintype "passive"))
      (node (ref "U19") (pin "1") (pinfunction "OUT1_1") (pintype "passive"))
    )
    (net (code "58") (name "Net-(U19B-+IN2)") (class "Default")
      (node (ref "R146") (pin "1") (pinfunction "1_1") (pintype "passive"))
      (node (ref "R148") (pin "2") (pinfunction "2_2") (pintype "passive"))
      (node (ref "U19") (pin "5") (pinfunction "+IN2_5") (pintype "passive"))
    )
    (net (code "59") (name "Net-(U19B--IN2)") (class "Default")
      (node (ref "R142") (pin "2") (pinfunction "2_2") (pintype "passive"))
      (node (ref "R144") (pin "1") (pinfunction "1_1") (pintype "passive"))
      (node (ref "U19") (pin "6") (pinfunction "-IN2_6") (pintype "passive"))
    )
    (net (code "60") (name "Net-(U19B-OUT2)") (class "Default")
      (node (ref "R142") (pin "1") (pinfunction "1_1") (pintype "passive"))
      (node (ref "R145") (pin "2") (pinfunction "2_2") (pintype "passive"))
      (node (ref "U19") (pin "7") (pinfunction "OUT2_7") (pintype "passive"))
    )
  )
)
